# USB.net
KiCad netlist of a schematic drawn in Altium Designer
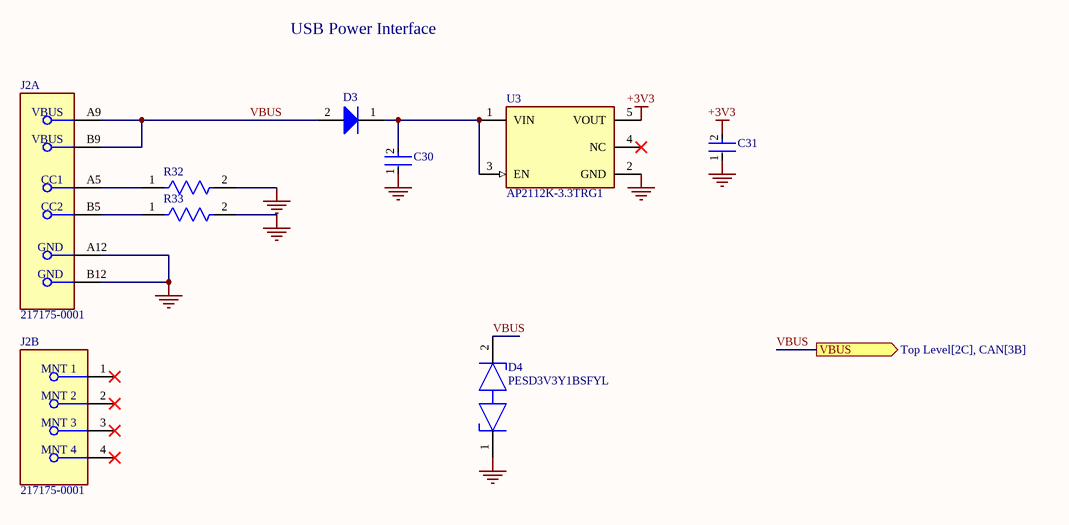
[diagram p0: USB.SchDoc]

(export (version "E")
  (design (tool "Eeschema 10.0.6"))
  (components
    (comp (ref "C30")
      (value "C1608X5R1H105K080AB")
      (footprint "FP-C1608-080-0_1-IPC_B")
      (description "Multilayer Ceramic Capacitors 1μF ±10% 50V X5R SMD 0603")
      (fields (field (name "VOLTAGE") "50V") (field (name "TOLERANCE") "10%"))
      (libsource (lib "Altium Content Vault") (part "236180d848d6139a670b325ea6854c9"))
    )
    (comp (ref "C31")
      (value "C1608X5R1H105K080AB")
      (footprint "FP-C1608-080-0_1-IPC_B")
      (description "Multilayer Ceramic Capacitors 1μF ±10% 50V X5R SMD 0603")
      (fields (field (name "VOLTAGE") "50V") (field (name "TOLERANCE") "10%"))
      (libsource (lib "Altium Content Vault") (part "236180d848d6139a670b325ea6854c9"))
    )
    (comp (ref "D3")
      (value "NSR0320MW2T1G")
      (footprint "ONSC-SOD-323-2-477-02_V")
      (description "Schottky Barrier Diode, 2-Pin SOD-323, Pb-Free, Tape and Reel")
      (fields (field (name "MANUFACTURER") "On Semiconductor"))
      (libsource (lib "Altium Content Vault") (part "ONSC-D-K1A2-2"))
    )
    (comp (ref "D4")
      (value "PESD3V3Y1BSFYL")
      (footprint "FP-SOD962-2-CA-MFG")
      (description "PESD3V3Y1BSFYL PESD4V0Y1BSF - Extremely low capacitance bidirectional ESD protection diode")
      (libsource (lib "Altium Content Vault") (part "3f15ade4c48aeaca3578241bea7d4a4"))
    )
    (comp (ref "J2")
      (value "217175-0001")
      (footprint "FP-217175-0001-MFG")
      (description "CONN RCP USB2.0 C 6+18P SMD RA")
      (libsource (lib "Altium Content Vault") (part "6a66c69350f09309f94811689c98437"))
    )
    (comp (ref "R32")
      (value "RN73R1ETTP5101F25")
      (footprint "FP-RN73R1E-IPC_C")
      (description "5.1kΩ ±1% 0.063W, 1/16W Chip Resistor 0402 (1005 Metric) Moisture Resistant Thin Film")
      (libsource (lib "Altium Content Vault") (part "1029c3af85768c4190bb7ad29bc67b5"))
    )
    (comp (ref "R33")
      (value "RN73R1ETTP5101F25")
      (footprint "FP-RN73R1E-IPC_C")
      (description "5.1kΩ ±1% 0.063W, 1/16W Chip Resistor 0402 (1005 Metric) Moisture Resistant Thin Film")
      (libsource (lib "Altium Content Vault") (part "1029c3af85768c4190bb7ad29bc67b5"))
    )
    (comp (ref "U3")
      (value "AP2112K-3.3TRG1")
      (footprint "FP-SOT25-IPC_A")
      (description "IC REG LINEAR 3.3V 600MA SOT25")
      (libsource (lib "Altium Content Vault") (part "c8ab751aee5229183125ab046a11caa"))
    )
  )
  (nets
    (net (code "1") (name "+3V3") (class "Default")
      (node (ref "C31") (pin "2") (pinfunction "2_2") (pintype "passive"))
      (node (ref "U3") (pin "5") (pinfunction "VOUT_5") (pintype "power_in"))
    )
    (net (code "2") (name "/VBUS") (class "Default")
      (node (ref "D3") (pin "2") (pinfunction "A_2") (pintype "passive"))
      (node (ref "D4") (pin "2") (pinfunction "2_2") (pintype "passive"))
      (node (ref "J2") (pin "A9") (pinfunction "VBUS_A9") (pintype "power_in"))
      (node (ref "J2") (pin "B9") (pinfunction "VBUS_B9") (pintype "power_in"))
    )
    (net (code "3") (name "GND") (class "Default")
      (node (ref "C30") (pin "1") (pinfunction "1_1") (pintype "passive"))
      (node (ref "C31") (pin "1") (pinfunction "1_1") (pintype "passive"))
      (node (ref "D4") (pin "1") (pinfunction "1_1") (pintype "passive"))
      (node (ref "J2") (pin "A12") (pinfunction "GND_A12") (pintype "power_in"))
      (node (ref "J2") (pin "B12") (pinfunction "GND_B12") (pintype "power_in"))
      (node (ref "R32") (pin "2") (pinfunction "2_2") (pintype "passive"))
      (node (ref "R33") (pin "2") (pinfunction "2_2") (pintype "passive"))
      (node (ref "U3") (pin "2") (pinfunction "GND_2") (pintype "power_in"))
    )
    (net (code "4") (name "Net-(D3-K)") (class "Default")
      (node (ref "C30") (pin "2") (pinfunction "2_2") (pintype "passive"))
      (node (ref "D3") (pin "1") (pinfunction "K_1") (pintype "passive"))
      (node (ref "U3") (pin "1") (pinfunction "VIN_1") (pintype "power_in"))
      (node (ref "U3") (pin "3") (pinfunction "EN_3") (pintype "input"))
    )
    (net (code "5") (name "Net-(J2A-CC1)") (class "Default")
      (node (ref "J2") (pin "A5") (pinfunction "CC1_A5") (pintype "passive"))
      (node (ref "R32") (pin "1") (pinfunction "1_1") (pintype "passive"))
    )
    (net (code "6") (name "Net-(J2A-CC2)") (class "Default")
      (node (ref "J2") (pin "B5") (pinfunction "CC2_B5") (pintype "passive"))
      (node (ref "R33") (pin "1") (pinfunction "1_1") (pintype "passive"))
    )
    (net (code "7") (name "unconnected-(J2B-MNT_1-Pad1)") (class "Default")
      (node (ref "J2") (pin "1") (pinfunction "MNT_1_1") (pintype "passive+no_connect"))
    )
    (net (code "8") (name "unconnected-(J2B-MNT_2-Pad2)") (class "Default")
      (node (ref "J2") (pin "2") (pinfunction "MNT_2_2") (pintype "passive+no_connect"))
    )
    (net (code "9") (name "unconnected-(J2B-MNT_3-Pad3)") (class "Default")
      (node (ref "J2") (pin "3") (pinfunction "MNT_3_3") (pintype "passive+no_connect"))
    )
    (net (code "10") (name "unconnected-(J2B-MNT_4-Pad4)") (class "Default")
      (node (ref "J2") (pin "4") (pinfunction "MNT_4_4") (pintype "passive+no_connect"))
    )
    (net (code "11") (name "unconnected-(U3-NC-Pad4)") (class "Default")
      (node (ref "U3") (pin "4") (pinfunction "NC_4") (pintype "passive+no_connect"))
    )
  )
)
